# SCH_customPCB_2026-04-30.net
KiCad netlist of a schematic drawn in EasyEDA
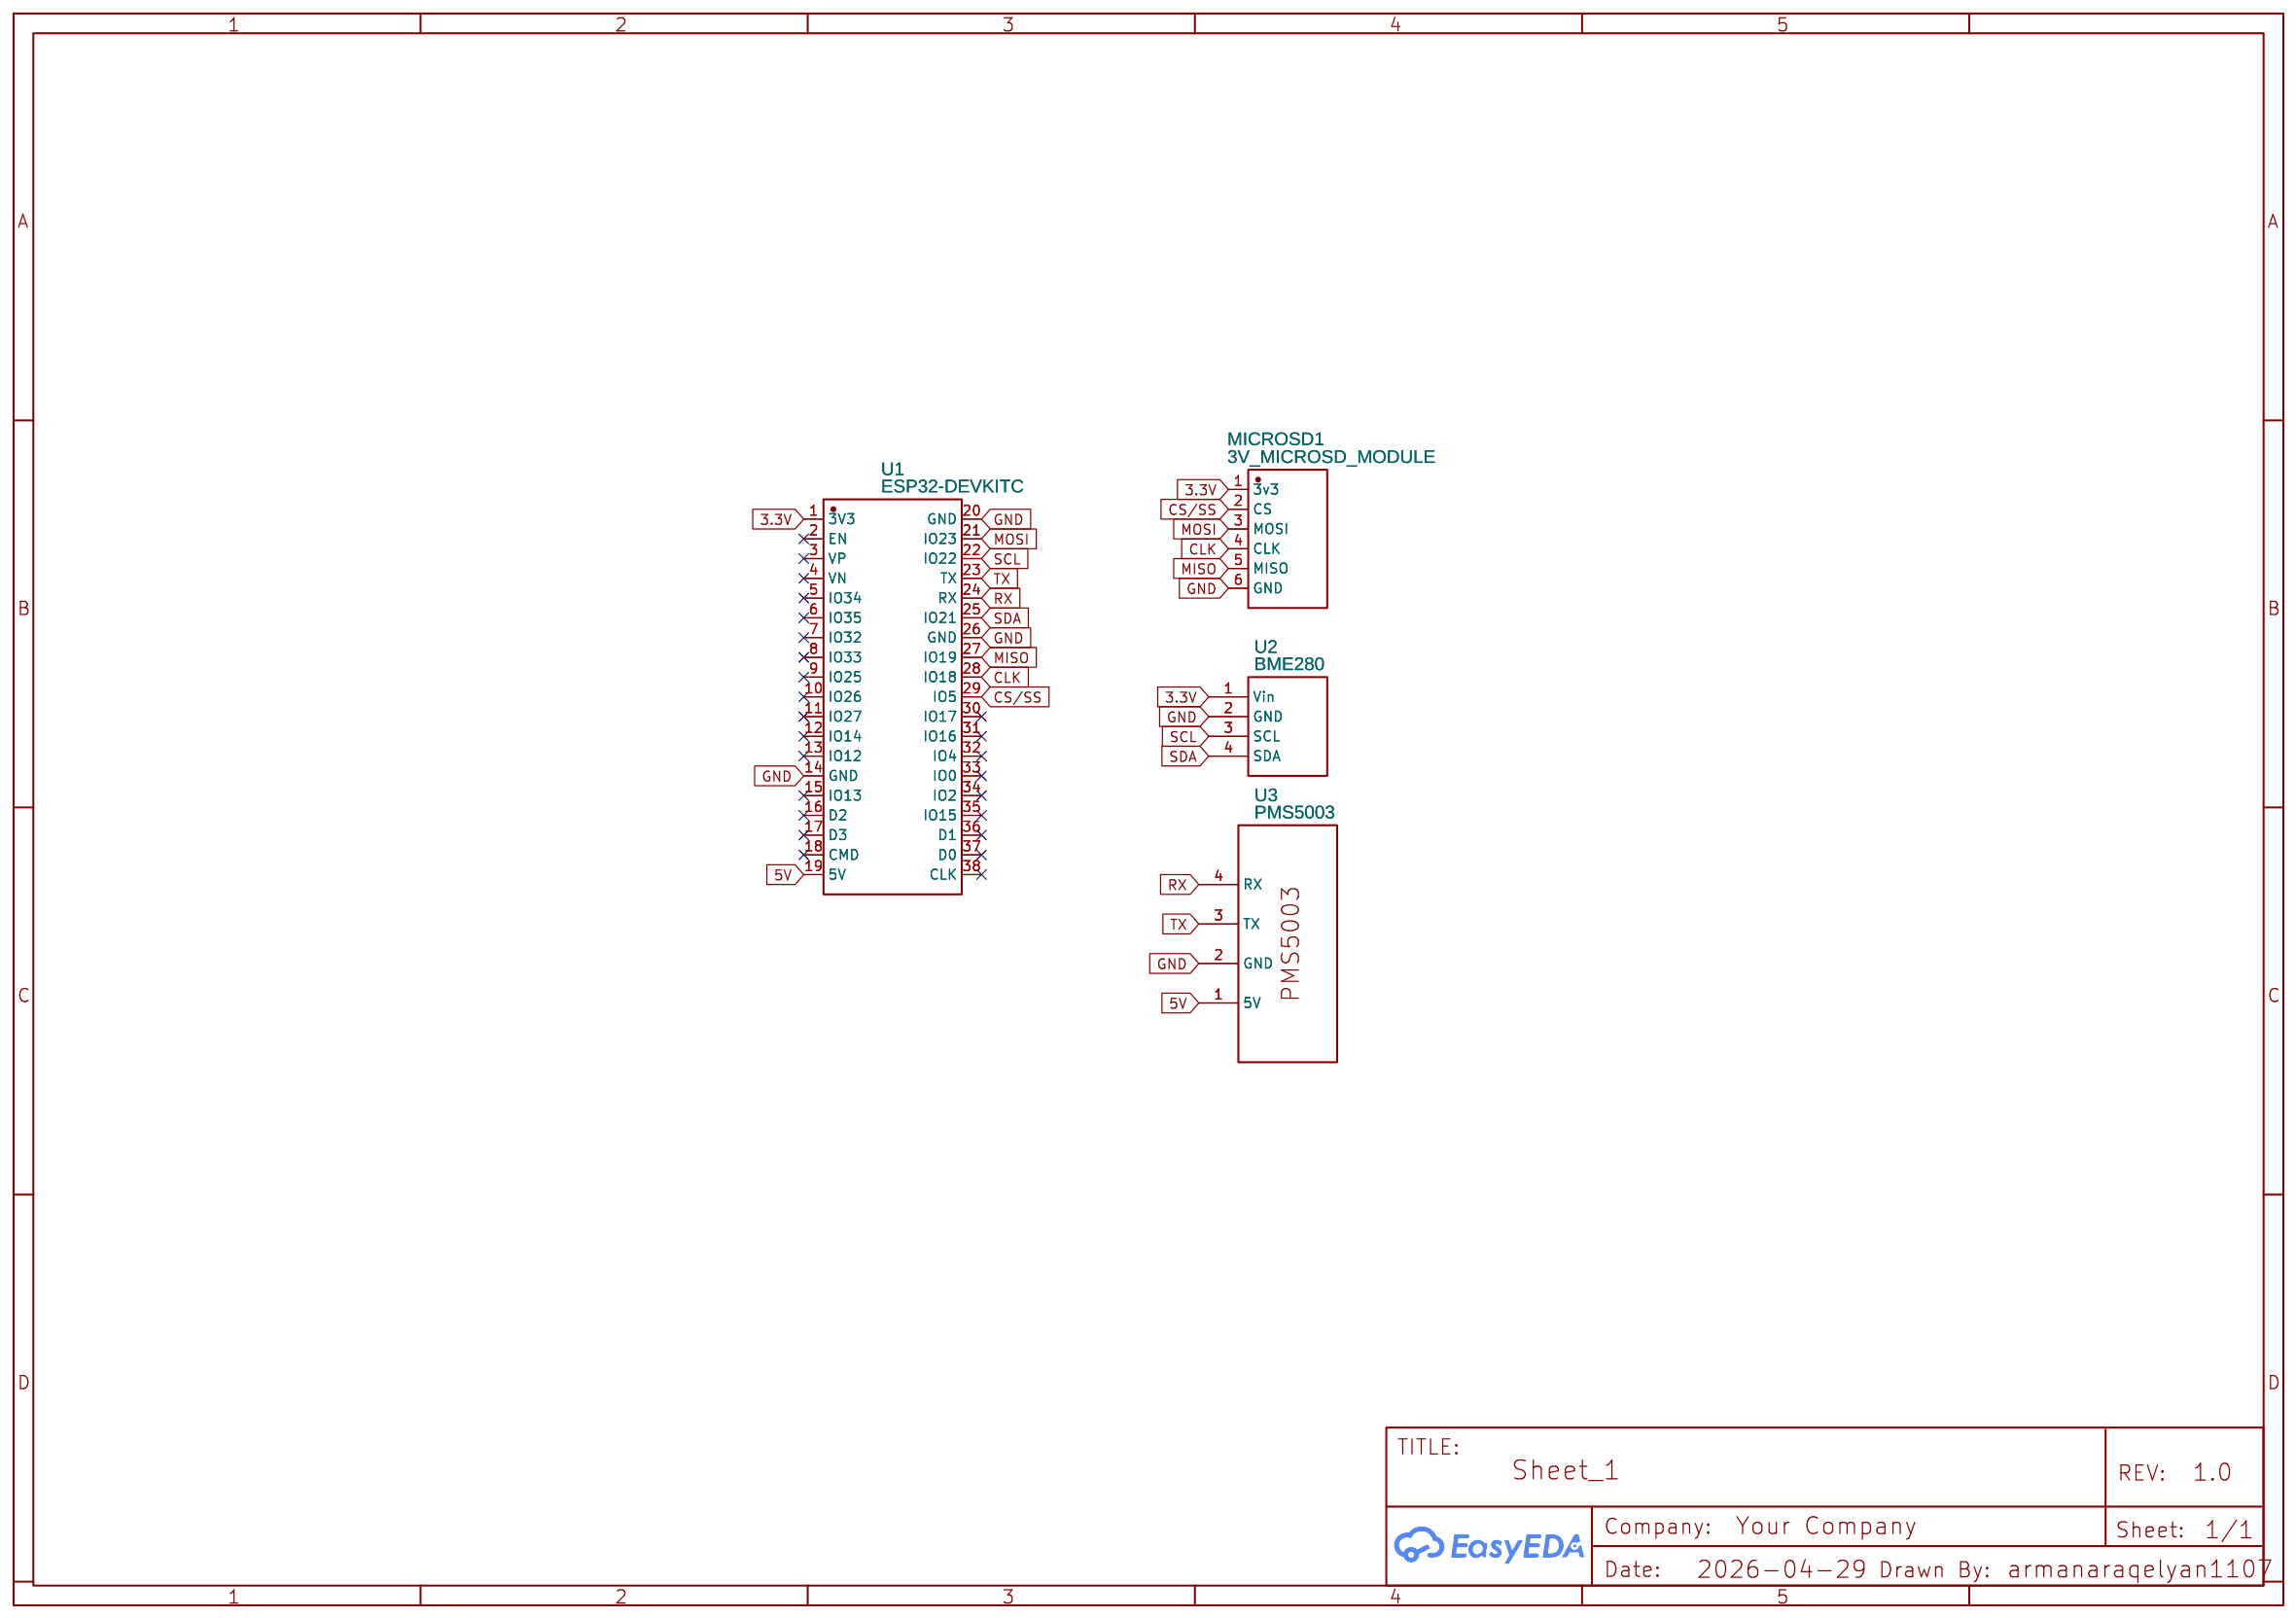
[diagram p0: schematic sheet]

(export (version "E")
  (design (tool "Eeschema 10.0.6"))
  (components
    (comp (ref "MICROSD1") (value "3V_MICROSD_MODULE") (libsource (lib "") (part "3V_MICROSD_MODULE")))
    (comp (ref "U1")
      (value "ESP32-DEVKITC")
      (fields
        (field (name "Manufacturer Part") "ESP32-DevKitC")
        (field (name "Manufacturer") "ESPRESSIF(乐鑫)")
      )
      (libsource (lib "") (part "ESP32-DEVKITC"))
    )
    (comp (ref "U2") (value "BME280") (libsource (lib "") (part "BME280")))
    (comp (ref "U3") (value "PMS5003") (libsource (lib "") (part "PMS5003")))
  )
  (nets
    (net (code "1") (name "3.3V") (class "Default")
      (node (ref "MICROSD1") (pin "1") (pinfunction "3v3_1") (pintype "unspecified"))
      (node (ref "U1") (pin "1") (pinfunction "3V3_1") (pintype "unspecified"))
      (node (ref "U2") (pin "1") (pinfunction "Vin_1") (pintype "unspecified"))
    )
    (net (code "2") (name "5V") (class "Default")
      (node (ref "U1") (pin "19") (pinfunction "5V_19") (pintype "unspecified"))
      (node (ref "U3") (pin "1") (pinfunction "5V_1") (pintype "unspecified"))
    )
    (net (code "3") (name "CLK") (class "Default")
      (node (ref "MICROSD1") (pin "4") (pinfunction "CLK_4") (pintype "unspecified"))
      (node (ref "U1") (pin "28") (pinfunction "IO18_28") (pintype "unspecified"))
    )
    (net (code "4") (name "CS{slash}SS") (class "Default")
      (node (ref "MICROSD1") (pin "2") (pinfunction "CS_2") (pintype "unspecified"))
      (node (ref "U1") (pin "29") (pinfunction "IO5_29") (pintype "unspecified"))
    )
    (net (code "5") (name "GND") (class "Default")
      (node (ref "MICROSD1") (pin "6") (pinfunction "GND_6") (pintype "unspecified"))
      (node (ref "U1") (pin "14") (pinfunction "GND_14") (pintype "unspecified"))
      (node (ref "U1") (pin "20") (pinfunction "GND_20") (pintype "unspecified"))
      (node (ref "U1") (pin "26") (pinfunction "GND_26") (pintype "unspecified"))
      (node (ref "U2") (pin "2") (pinfunction "GND_2") (pintype "unspecified"))
      (node (ref "U3") (pin "2") (pinfunction "GND_2") (pintype "unspecified"))
    )
    (net (code "6") (name "MISO") (class "Default")
      (node (ref "MICROSD1") (pin "5") (pinfunction "MISO_5") (pintype "unspecified"))
      (node (ref "U1") (pin "27") (pinfunction "IO19_27") (pintype "unspecified"))
    )
    (net (code "7") (name "MOSI") (class "Default")
      (node (ref "MICROSD1") (pin "3") (pinfunction "MOSI_3") (pintype "unspecified"))
      (node (ref "U1") (pin "21") (pinfunction "IO23_21") (pintype "unspecified"))
    )
    (net (code "8") (name "RX") (class "Default")
      (node (ref "U1") (pin "24") (pinfunction "RX_24") (pintype "unspecified"))
      (node (ref "U3") (pin "4") (pinfunction "RX_4") (pintype "unspecified"))
    )
    (net (code "9") (name "SCL") (class "Default")
      (node (ref "U1") (pin "22") (pinfunction "IO22_22") (pintype "unspecified"))
      (node (ref "U2") (pin "3") (pinfunction "SCL_3") (pintype "unspecified"))
    )
    (net (code "10") (name "SDA") (class "Default")
      (node (ref "U1") (pin "25") (pinfunction "IO21_25") (pintype "unspecified"))
      (node (ref "U2") (pin "4") (pinfunction "SDA_4") (pintype "unspecified"))
    )
    (net (code "11") (name "TX") (class "Default")
      (node (ref "U1") (pin "23") (pinfunction "TX_23") (pintype "unspecified"))
      (node (ref "U3") (pin "3") (pinfunction "TX_3") (pintype "unspecified"))
    )
    (net (code "12") (name "unconnected-(U1-CLK-Pad38)") (class "Default")
      (node (ref "U1") (pin "38") (pinfunction "CLK_38") (pintype "unspecified+no_connect"))
    )
    (net (code "13") (name "unconnected-(U1-CMD-Pad18)") (class "Default")
      (node (ref "U1") (pin "18") (pinfunction "CMD_18") (pintype "unspecified+no_connect"))
    )
    (net (code "14") (name "unconnected-(U1-D0-Pad37)") (class "Default")
      (node (ref "U1") (pin "37") (pinfunction "D0_37") (pintype "unspecified+no_connect"))
    )
    (net (code "15") (name "unconnected-(U1-D1-Pad36)") (class "Default")
      (node (ref "U1") (pin "36") (pinfunction "D1_36") (pintype "unspecified+no_connect"))
    )
    (net (code "16") (name "unconnected-(U1-D2-Pad16)") (class "Default")
      (node (ref "U1") (pin "16") (pinfunction "D2_16") (pintype "unspecified+no_connect"))
    )
    (net (code "17") (name "unconnected-(U1-D3-Pad17)") (class "Default")
      (node (ref "U1") (pin "17") (pinfunction "D3_17") (pintype "unspecified+no_connect"))
    )
    (net (code "18") (name "unconnected-(U1-EN-Pad2)") (class "Default")
      (node (ref "U1") (pin "2") (pinfunction "EN_2") (pintype "unspecified+no_connect"))
    )
    (net (code "19") (name "unconnected-(U1-IO0-Pad33)") (class "Default")
      (node (ref "U1") (pin "33") (pinfunction "IO0_33") (pintype "unspecified+no_connect"))
    )
    (net (code "20") (name "unconnected-(U1-IO2-Pad34)") (class "Default")
      (node (ref "U1") (pin "34") (pinfunction "IO2_34") (pintype "unspecified+no_connect"))
    )
    (net (code "21") (name "unconnected-(U1-IO4-Pad32)") (class "Default")
      (node (ref "U1") (pin "32") (pinfunction "IO4_32") (pintype "unspecified+no_connect"))
    )
    (net (code "22") (name "unconnected-(U1-IO12-Pad13)") (class "Default")
      (node (ref "U1") (pin "13") (pinfunction "IO12_13") (pintype "unspecified+no_connect"))
    )
    (net (code "23") (name "unconnected-(U1-IO13-Pad15)") (class "Default")
      (node (ref "U1") (pin "15") (pinfunction "IO13_15") (pintype "unspecified+no_connect"))
    )
    (net (code "24") (name "unconnected-(U1-IO14-Pad12)") (class "Default")
      (node (ref "U1") (pin "12") (pinfunction "IO14_12") (pintype "unspecified+no_connect"))
    )
    (net (code "25") (name "unconnected-(U1-IO15-Pad35)") (class "Default")
      (node (ref "U1") (pin "35") (pinfunction "IO15_35") (pintype "unspecified+no_connect"))
    )
    (net (code "26") (name "unconnected-(U1-IO16-Pad31)") (class "Default")
      (node (ref "U1") (pin "31") (pinfunction "IO16_31") (pintype "unspecified+no_connect"))
    )
    (net (code "27") (name "unconnected-(U1-IO17-Pad30)") (class "Default")
      (node (ref "U1") (pin "30") (pinfunction "IO17_30") (pintype "unspecified+no_connect"))
    )
    (net (code "28") (name "unconnected-(U1-IO25-Pad9)") (class "Default")
      (node (ref "U1") (pin "9") (pinfunction "IO25_9") (pintype "unspecified+no_connect"))
    )
    (net (code "29") (name "unconnected-(U1-IO26-Pad10)") (class "Default")
      (node (ref "U1") (pin "10") (pinfunction "IO26_10") (pintype "unspecified+no_connect"))
    )
    (net (code "30") (name "unconnected-(U1-IO27-Pad11)") (class "Default")
      (node (ref "U1") (pin "11") (pinfunction "IO27_11") (pintype "unspecified+no_connect"))
    )
    (net (code "31") (name "unconnected-(U1-IO32-Pad7)") (class "Default")
      (node (ref "U1") (pin "7") (pinfunction "IO32_7") (pintype "unspecified+no_connect"))
    )
    (net (code "32") (name "unconnected-(U1-IO33-Pad8)") (class "Default")
      (node (ref "U1") (pin "8") (pinfunction "IO33_8") (pintype "unspecified+no_connect"))
    )
    (net (code "33") (name "unconnected-(U1-IO34-Pad5)") (class "Default")
      (node (ref "U1") (pin "5") (pinfunction "IO34_5") (pintype "unspecified+no_connect"))
    )
    (net (code "34") (name "unconnected-(U1-IO35-Pad6)") (class "Default")
      (node (ref "U1") (pin "6") (pinfunction "IO35_6") (pintype "unspecified+no_connect"))
    )
    (net (code "35") (name "unconnected-(U1-VN-Pad4)") (class "Default")
      (node (ref "U1") (pin "4") (pinfunction "VN_4") (pintype "unspecified+no_connect"))
    )
    (net (code "36") (name "unconnected-(U1-VP-Pad3)") (class "Default")
      (node (ref "U1") (pin "3") (pinfunction "VP_3") (pintype "unspecified+no_connect"))
    )
  )
)
